# Lampduino-SMD-v001.net
KiCad netlist of a schematic drawn in EAGLE
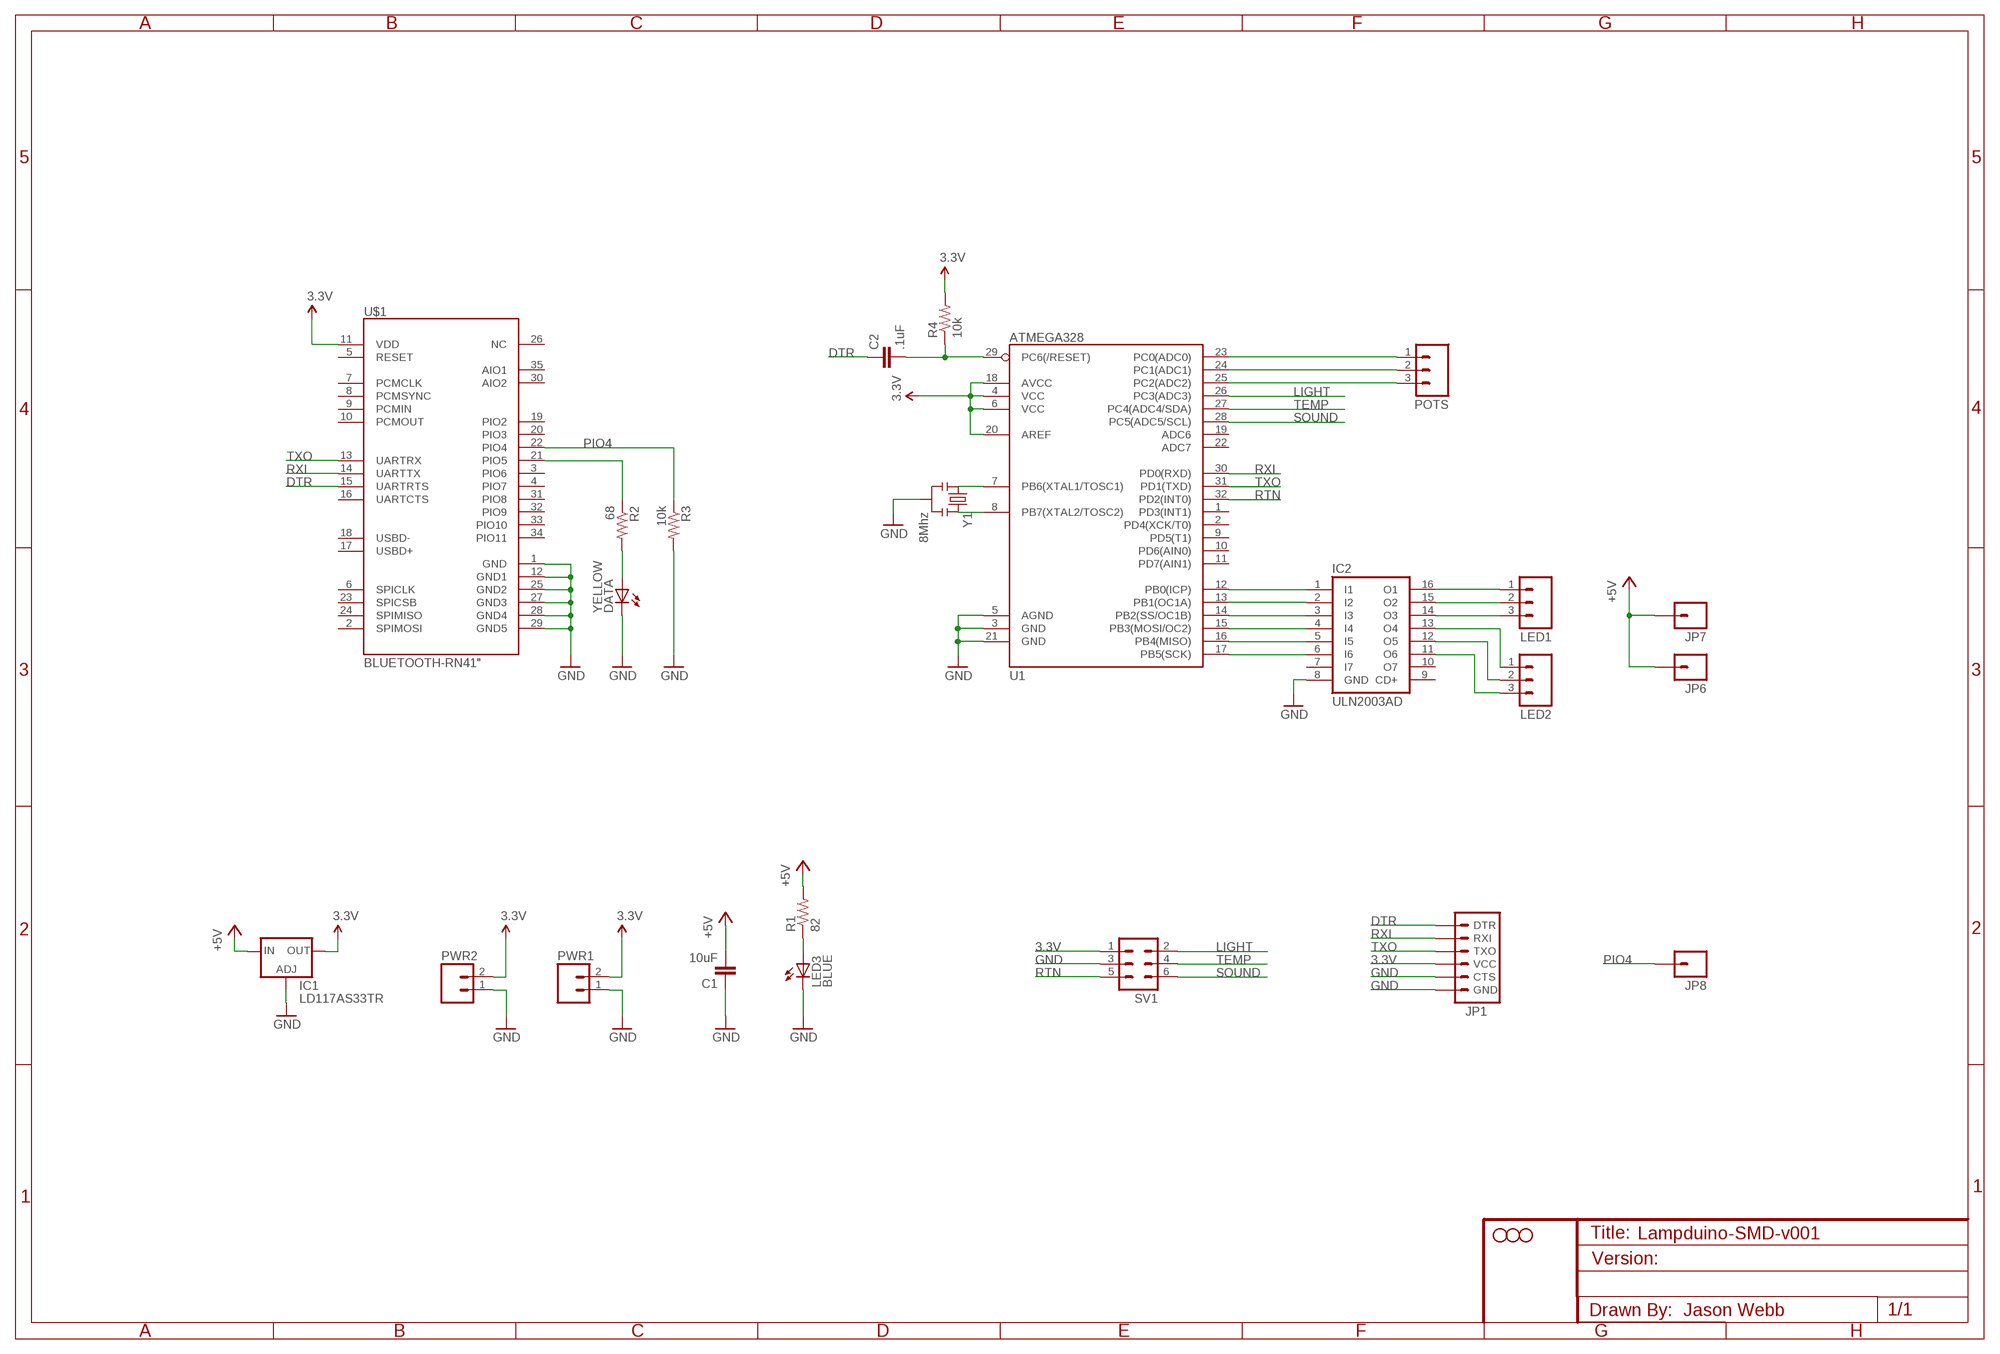
[diagram p0: schematic, sheet 1]

(export (version "E")
  (design (tool "Eeschema 10.0.6"))
  (components
    (comp (ref "C1")
      (value "10uF")
      (footprint "eagle-import:0805")
      (libsource (lib "eagle-import") (part "CAP0805"))
    )
    (comp (ref "C2")
      (value ".1uF")
      (footprint "eagle-import:0805")
      (libsource (lib "eagle-import") (part "CAP0805"))
    )
    (comp (ref "DATA")
      (value "YELLOW")
      (footprint "eagle-import:CHIPLED_0603")
      (libsource (lib "eagle-import") (part "LEDCHIPLED_0603"))
    )
    (comp (ref "IC1")
      (value "LD117AS33TR")
      (footprint "eagle-import:SOT223")
      (libsource (lib "eagle-import") (part "LD117A?S33TR"))
    )
    (comp (ref "IC2")
      (value "ULN2003AD")
      (footprint "eagle-import:SO16")
      (libsource (lib "eagle-import") (part "ULN2003AD"))
    )
    (comp (ref "JP1")
      (value "ARDUINO_SERIAL_PROGRAMLOCK")
      (footprint "eagle-import:1X06_LOCK")
      (libsource (lib "eagle-import") (part "ARDUINO_SERIAL_PROGRAMLOCK"))
    )
    (comp (ref "JP2")
      (value "STAND-OFFTIGHT")
      (footprint "eagle-import:STAND-OFF-TIGHT")
      (libsource (lib "eagle-import") (part "STAND-OFFTIGHT"))
    )
    (comp (ref "JP4")
      (value "STAND-OFFTIGHT")
      (footprint "eagle-import:STAND-OFF-TIGHT")
      (libsource (lib "eagle-import") (part "STAND-OFFTIGHT"))
    )
    (comp (ref "JP5")
      (value "STAND-OFFTIGHT")
      (footprint "eagle-import:STAND-OFF-TIGHT")
      (libsource (lib "eagle-import") (part "STAND-OFFTIGHT"))
    )
    (comp (ref "JP6")
      (value "M01PTH")
      (footprint "eagle-import:1X01")
      (libsource (lib "eagle-import") (part "M01PTH"))
    )
    (comp (ref "JP7")
      (value "M01PTH")
      (footprint "eagle-import:1X01")
      (libsource (lib "eagle-import") (part "M01PTH"))
    )
    (comp (ref "JP8")
      (value "M01PTH")
      (footprint "eagle-import:1X01")
      (libsource (lib "eagle-import") (part "M01PTH"))
    )
    (comp (ref "LED1")
      (value "M03PTH")
      (footprint "eagle-import:1X03")
      (libsource (lib "eagle-import") (part "M03PTH"))
    )
    (comp (ref "LED2")
      (value "M03PTH")
      (footprint "eagle-import:1X03")
      (libsource (lib "eagle-import") (part "M03PTH"))
    )
    (comp (ref "LED3")
      (value "BLUE")
      (footprint "eagle-import:CHIPLED_0603")
      (libsource (lib "eagle-import") (part "LEDCHIPLED_0603"))
    )
    (comp (ref "POTS")
      (value "M03PTH")
      (footprint "eagle-import:1X03")
      (libsource (lib "eagle-import") (part "M03PTH"))
    )
    (comp (ref "PWR1")
      (value "M02PTH")
      (footprint "eagle-import:1X02")
      (libsource (lib "eagle-import") (part "M02PTH"))
    )
    (comp (ref "PWR2")
      (value "M02PTH")
      (footprint "eagle-import:1X02")
      (libsource (lib "eagle-import") (part "M02PTH"))
    )
    (comp (ref "R1")
      (value "82")
      (footprint "eagle-import:R0603")
      (libsource (lib "eagle-import") (part "R-US_R0603"))
    )
    (comp (ref "R2")
      (value "68")
      (footprint "eagle-import:R0603")
      (libsource (lib "eagle-import") (part "R-US_R0603"))
    )
    (comp (ref "R3")
      (value "10k")
      (footprint "eagle-import:R0603")
      (libsource (lib "eagle-import") (part "R-US_R0603"))
    )
    (comp (ref "R4")
      (value "10k")
      (footprint "eagle-import:R0603")
      (libsource (lib "eagle-import") (part "R-US_R0603"))
    )
    (comp (ref "SV1")
      (value "ML6")
      (footprint "eagle-import:ML6")
      (libsource (lib "eagle-import") (part "ML6"))
    )
    (comp (ref "U$1")
      (value "BLUETOOTH-RN41\"")
      (footprint "eagle-import:RN41")
      (libsource (lib "eagle-import") (part "BLUETOOTH-RN41{dblquote}"))
    )
    (comp (ref "U1")
      (value "ATMEGA328")
      (footprint "eagle-import:TQFP32-08")
      (libsource (lib "eagle-import") (part "ATMEGA168"))
    )
    (comp (ref "Y1")
      (value "8Mhz")
      (footprint "eagle-import:RESONATOR-SMD")
      (libsource (lib "eagle-import") (part "RESONATORSMD"))
    )
  )
  (nets
    (net (code "1") (name "+5V") (class "Default")
      (node (ref "C1") (pin "2") (pinfunction "2_2") (pintype "passive"))
      (node (ref "IC1") (pin "3") (pinfunction "IN_3") (pintype "input"))
      (node (ref "JP6") (pin "1") (pinfunction "1_1") (pintype "passive"))
      (node (ref "JP7") (pin "1") (pinfunction "1_1") (pintype "passive"))
      (node (ref "R1") (pin "2") (pinfunction "2_2") (pintype "passive"))
    )
    (net (code "2") (name "/DTR") (class "Default")
      (node (ref "C2") (pin "1") (pinfunction "1_1") (pintype "passive"))
      (node (ref "JP1") (pin "1") (pinfunction "DTR_1") (pintype "passive"))
      (node (ref "U$1") (pin "15") (pinfunction "UARTRTS_15") (pintype "bidirectional"))
    )
    (net (code "3") (name "/LIGHT") (class "Default")
      (node (ref "SV1") (pin "2") (pinfunction "2_2") (pintype "passive"))
      (node (ref "U1") (pin "26") (pinfunction "PC3(ADC3)_26") (pintype "bidirectional"))
    )
    (net (code "4") (name "/PIO4") (class "Default")
      (node (ref "JP8") (pin "1") (pinfunction "1_1") (pintype "passive"))
      (node (ref "R3") (pin "1") (pinfunction "1_1") (pintype "passive"))
      (node (ref "U$1") (pin "22") (pinfunction "PIO4_22") (pintype "bidirectional"))
    )
    (net (code "5") (name "/RTN") (class "Default")
      (node (ref "SV1") (pin "5") (pinfunction "5_5") (pintype "passive"))
      (node (ref "U1") (pin "32") (pinfunction "PD2(INT0)_32") (pintype "bidirectional"))
    )
    (net (code "6") (name "/RXI") (class "Default")
      (node (ref "JP1") (pin "2") (pinfunction "RXI_2") (pintype "passive"))
      (node (ref "U$1") (pin "14") (pinfunction "UARTTX_14") (pintype "bidirectional"))
      (node (ref "U1") (pin "30") (pinfunction "PD0(RXD)_30") (pintype "bidirectional"))
    )
    (net (code "7") (name "/SOUND") (class "Default")
      (node (ref "SV1") (pin "6") (pinfunction "6_6") (pintype "passive"))
      (node (ref "U1") (pin "28") (pinfunction "PC5(ADC5/SCL)_28") (pintype "bidirectional"))
    )
    (net (code "8") (name "/TEMP") (class "Default")
      (node (ref "SV1") (pin "4") (pinfunction "4_4") (pintype "passive"))
      (node (ref "U1") (pin "27") (pinfunction "PC4(ADC4/SDA)_27") (pintype "bidirectional"))
    )
    (net (code "9") (name "/TXO") (class "Default")
      (node (ref "JP1") (pin "3") (pinfunction "TXO_3") (pintype "passive"))
      (node (ref "U$1") (pin "13") (pinfunction "UARTRX_13") (pintype "bidirectional"))
      (node (ref "U1") (pin "31") (pinfunction "PD1(TXD)_31") (pintype "bidirectional"))
    )
    (net (code "10") (name "3.3V") (class "Default")
      (node (ref "IC1") (pin "4") (pinfunction "OUT_4") (pintype "passive"))
      (node (ref "JP1") (pin "4") (pinfunction "VCC_4") (pintype "passive"))
      (node (ref "PWR1") (pin "2") (pinfunction "2_2") (pintype "passive"))
      (node (ref "PWR2") (pin "2") (pinfunction "2_2") (pintype "passive"))
      (node (ref "R4") (pin "2") (pinfunction "2_2") (pintype "passive"))
      (node (ref "SV1") (pin "1") (pinfunction "1_1") (pintype "passive"))
      (node (ref "U$1") (pin "11") (pinfunction "VDD_11") (pintype "bidirectional"))
      (node (ref "U1") (pin "18") (pinfunction "AVCC_18") (pintype "bidirectional"))
      (node (ref "U1") (pin "20") (pinfunction "AREF_20") (pintype "bidirectional"))
      (node (ref "U1") (pin "4") (pinfunction "VCC_4") (pintype "bidirectional"))
      (node (ref "U1") (pin "6") (pinfunction "VCC_6") (pintype "bidirectional"))
    )
    (net (code "11") (name "GND") (class "Default")
      (node (ref "C1") (pin "1") (pinfunction "1_1") (pintype "passive"))
      (node (ref "DATA") (pin "C") (pinfunction "C_C") (pintype "passive"))
      (node (ref "IC1") (pin "1") (pinfunction "ADJ_1") (pintype "input"))
      (node (ref "IC2") (pin "8") (pinfunction "GND_8") (pintype "power_in"))
      (node (ref "JP1") (pin "5") (pinfunction "CTS_5") (pintype "passive"))
      (node (ref "JP1") (pin "6") (pinfunction "GND_6") (pintype "passive"))
      (node (ref "LED3") (pin "C") (pinfunction "C_C") (pintype "passive"))
      (node (ref "PWR1") (pin "1") (pinfunction "1_1") (pintype "passive"))
      (node (ref "PWR2") (pin "1") (pinfunction "1_1") (pintype "passive"))
      (node (ref "R3") (pin "2") (pinfunction "2_2") (pintype "passive"))
      (node (ref "SV1") (pin "3") (pinfunction "3_3") (pintype "passive"))
      (node (ref "U$1") (pin "1") (pinfunction "GND_1") (pintype "bidirectional"))
      (node (ref "U$1") (pin "12") (pinfunction "GND1_12") (pintype "bidirectional"))
      (node (ref "U$1") (pin "25") (pinfunction "GND2_25") (pintype "bidirectional"))
      (node (ref "U$1") (pin "27") (pinfunction "GND3_27") (pintype "bidirectional"))
      (node (ref "U$1") (pin "28") (pinfunction "GND4_28") (pintype "bidirectional"))
      (node (ref "U$1") (pin "29") (pinfunction "GND5_29") (pintype "bidirectional"))
      (node (ref "U1") (pin "21") (pinfunction "GND_21") (pintype "bidirectional"))
      (node (ref "U1") (pin "3") (pinfunction "GND_3") (pintype "bidirectional"))
      (node (ref "U1") (pin "5") (pinfunction "AGND_5") (pintype "bidirectional"))
      (node (ref "Y1") (pin "2") (pinfunction "2_2") (pintype "passive"))
    )
    (net (code "12") (name "Net-(DATA-PadA)") (class "Default")
      (node (ref "DATA") (pin "A") (pinfunction "A_A") (pintype "passive"))
      (node (ref "R2") (pin "2") (pinfunction "2_2") (pintype "passive"))
    )
    (net (code "13") (name "Net-(IC2-I1)") (class "Default")
      (node (ref "IC2") (pin "1") (pinfunction "I1_1") (pintype "input"))
      (node (ref "U1") (pin "12") (pinfunction "PB0(ICP)_12") (pintype "bidirectional"))
    )
    (net (code "14") (name "Net-(IC2-I2)") (class "Default")
      (node (ref "IC2") (pin "2") (pinfunction "I2_2") (pintype "input"))
      (node (ref "U1") (pin "13") (pinfunction "PB1(OC1A)_13") (pintype "bidirectional"))
    )
    (net (code "15") (name "Net-(IC2-I3)") (class "Default")
      (node (ref "IC2") (pin "3") (pinfunction "I3_3") (pintype "input"))
      (node (ref "U1") (pin "14") (pinfunction "PB2(SS/OC1B)_14") (pintype "bidirectional"))
    )
    (net (code "16") (name "Net-(IC2-I4)") (class "Default")
      (node (ref "IC2") (pin "4") (pinfunction "I4_4") (pintype "input"))
      (node (ref "U1") (pin "15") (pinfunction "PB3(MOSI/OC2)_15") (pintype "bidirectional"))
    )
    (net (code "17") (name "Net-(IC2-I5)") (class "Default")
      (node (ref "IC2") (pin "5") (pinfunction "I5_5") (pintype "input"))
      (node (ref "U1") (pin "16") (pinfunction "PB4(MISO)_16") (pintype "bidirectional"))
    )
    (net (code "18") (name "Net-(IC2-I6)") (class "Default")
      (node (ref "IC2") (pin "6") (pinfunction "I6_6") (pintype "input"))
      (node (ref "U1") (pin "17") (pinfunction "PB5(SCK)_17") (pintype "bidirectional"))
    )
    (net (code "19") (name "Net-(IC2-O1)") (class "Default")
      (node (ref "IC2") (pin "16") (pinfunction "O1_16") (pintype "open_collector"))
      (node (ref "LED1") (pin "1") (pinfunction "1_1") (pintype "passive"))
    )
    (net (code "20") (name "Net-(IC2-O2)") (class "Default")
      (node (ref "IC2") (pin "15") (pinfunction "O2_15") (pintype "open_collector"))
      (node (ref "LED1") (pin "2") (pinfunction "2_2") (pintype "passive"))
    )
    (net (code "21") (name "Net-(IC2-O3)") (class "Default")
      (node (ref "IC2") (pin "14") (pinfunction "O3_14") (pintype "open_collector"))
      (node (ref "LED1") (pin "3") (pinfunction "3_3") (pintype "passive"))
    )
    (net (code "22") (name "Net-(IC2-O4)") (class "Default")
      (node (ref "IC2") (pin "13") (pinfunction "O4_13") (pintype "open_collector"))
      (node (ref "LED2") (pin "1") (pinfunction "1_1") (pintype "passive"))
    )
    (net (code "23") (name "Net-(IC2-O5)") (class "Default")
      (node (ref "IC2") (pin "12") (pinfunction "O5_12") (pintype "open_collector"))
      (node (ref "LED2") (pin "2") (pinfunction "2_2") (pintype "passive"))
    )
    (net (code "24") (name "Net-(IC2-O6)") (class "Default")
      (node (ref "IC2") (pin "11") (pinfunction "O6_11") (pintype "open_collector"))
      (node (ref "LED2") (pin "3") (pinfunction "3_3") (pintype "passive"))
    )
    (net (code "25") (name "Net-(LED3-PadA)") (class "Default")
      (node (ref "LED3") (pin "A") (pinfunction "A_A") (pintype "passive"))
      (node (ref "R1") (pin "1") (pinfunction "1_1") (pintype "passive"))
    )
    (net (code "26") (name "Net-(U$1-PIO5)") (class "Default")
      (node (ref "R2") (pin "1") (pinfunction "1_1") (pintype "passive"))
      (node (ref "U$1") (pin "21") (pinfunction "PIO5_21") (pintype "bidirectional"))
    )
    (net (code "27") (name "Net-(U1-PB6(XTAL1{slash}TOSC1))") (class "Default")
      (node (ref "U1") (pin "7") (pinfunction "PB6(XTAL1/TOSC1)_7") (pintype "bidirectional"))
      (node (ref "Y1") (pin "1") (pinfunction "1_1") (pintype "passive"))
    )
    (net (code "28") (name "Net-(U1-PB7(XTAL2{slash}TOSC2))") (class "Default")
      (node (ref "U1") (pin "8") (pinfunction "PB7(XTAL2/TOSC2)_8") (pintype "bidirectional"))
      (node (ref "Y1") (pin "3") (pinfunction "3_3") (pintype "passive"))
    )
    (net (code "29") (name "Net-(U1-PC0(ADC0))") (class "Default")
      (node (ref "POTS") (pin "1") (pinfunction "1_1") (pintype "passive"))
      (node (ref "U1") (pin "23") (pinfunction "PC0(ADC0)_23") (pintype "bidirectional"))
    )
    (net (code "30") (name "Net-(U1-PC1(ADC1))") (class "Default")
      (node (ref "POTS") (pin "2") (pinfunction "2_2") (pintype "passive"))
      (node (ref "U1") (pin "24") (pinfunction "PC1(ADC1)_24") (pintype "bidirectional"))
    )
    (net (code "31") (name "Net-(U1-PC2(ADC2))") (class "Default")
      (node (ref "POTS") (pin "3") (pinfunction "3_3") (pintype "passive"))
      (node (ref "U1") (pin "25") (pinfunction "PC2(ADC2)_25") (pintype "bidirectional"))
    )
    (net (code "32") (name "Net-(U1-PC6({slash}RESET))") (class "Default")
      (node (ref "C2") (pin "2") (pinfunction "2_2") (pintype "passive"))
      (node (ref "R4") (pin "1") (pinfunction "1_1") (pintype "passive"))
      (node (ref "U1") (pin "29") (pinfunction "PC6(/RESET)_29") (pintype "bidirectional"))
    )
    (net (code "33") (name "unconnected-(IC2-CD+-Pad9)") (class "Default")
      (node (ref "IC2") (pin "9") (pinfunction "CD+_9") (pintype "passive"))
    )
    (net (code "34") (name "unconnected-(IC2-I7-Pad7)") (class "Default")
      (node (ref "IC2") (pin "7") (pinfunction "I7_7") (pintype "input"))
    )
    (net (code "35") (name "unconnected-(IC2-O7-Pad10)") (class "Default")
      (node (ref "IC2") (pin "10") (pinfunction "O7_10") (pintype "open_collector"))
    )
    (net (code "36") (name "unconnected-(U$1-AIO1-Pad35)") (class "Default")
      (node (ref "U$1") (pin "35") (pinfunction "AIO1_35") (pintype "bidirectional"))
    )
    (net (code "37") (name "unconnected-(U$1-AIO2-Pad30)") (class "Default")
      (node (ref "U$1") (pin "30") (pinfunction "AIO2_30") (pintype "bidirectional"))
    )
    (net (code "38") (name "unconnected-(U$1-NC-Pad26)") (class "Default")
      (node (ref "U$1") (pin "26") (pinfunction "NC_26") (pintype "bidirectional"))
    )
    (net (code "39") (name "unconnected-(U$1-PCMCLK-Pad7)") (class "Default")
      (node (ref "U$1") (pin "7") (pinfunction "PCMCLK_7") (pintype "bidirectional"))
    )
    (net (code "40") (name "unconnected-(U$1-PCMIN-Pad9)") (class "Default")
      (node (ref "U$1") (pin "9") (pinfunction "PCMIN_9") (pintype "bidirectional"))
    )
    (net (code "41") (name "unconnected-(U$1-PCMOUT-Pad10)") (class "Default")
      (node (ref "U$1") (pin "10") (pinfunction "PCMOUT_10") (pintype "bidirectional"))
    )
    (net (code "42") (name "unconnected-(U$1-PCMSYNC-Pad8)") (class "Default")
      (node (ref "U$1") (pin "8") (pinfunction "PCMSYNC_8") (pintype "bidirectional"))
    )
    (net (code "43") (name "unconnected-(U$1-PIO2-Pad19)") (class "Default")
      (node (ref "U$1") (pin "19") (pinfunction "PIO2_19") (pintype "bidirectional"))
    )
    (net (code "44") (name "unconnected-(U$1-PIO3-Pad20)") (class "Default")
      (node (ref "U$1") (pin "20") (pinfunction "PIO3_20") (pintype "bidirectional"))
    )
    (net (code "45") (name "unconnected-(U$1-PIO6-Pad3)") (class "Default")
      (node (ref "U$1") (pin "3") (pinfunction "PIO6_3") (pintype "bidirectional"))
    )
    (net (code "46") (name "unconnected-(U$1-PIO7-Pad4)") (class "Default")
      (node (ref "U$1") (pin "4") (pinfunction "PIO7_4") (pintype "bidirectional"))
    )
    (net (code "47") (name "unconnected-(U$1-PIO8-Pad31)") (class "Default")
      (node (ref "U$1") (pin "31") (pinfunction "PIO8_31") (pintype "bidirectional"))
    )
    (net (code "48") (name "unconnected-(U$1-PIO9-Pad32)") (class "Default")
      (node (ref "U$1") (pin "32") (pinfunction "PIO9_32") (pintype "bidirectional"))
    )
    (net (code "49") (name "unconnected-(U$1-PIO10-Pad33)") (class "Default")
      (node (ref "U$1") (pin "33") (pinfunction "PIO10_33") (pintype "bidirectional"))
    )
    (net (code "50") (name "unconnected-(U$1-PIO11-Pad34)") (class "Default")
      (node (ref "U$1") (pin "34") (pinfunction "PIO11_34") (pintype "bidirectional"))
    )
    (net (code "51") (name "unconnected-(U$1-RESET-Pad5)") (class "Default")
      (node (ref "U$1") (pin "5") (pinfunction "RESET_5") (pintype "bidirectional"))
    )
    (net (code "52") (name "unconnected-(U$1-SPICLK-Pad6)") (class "Default")
      (node (ref "U$1") (pin "6") (pinfunction "SPICLK_6") (pintype "bidirectional"))
    )
    (net (code "53") (name "unconnected-(U$1-SPICSB-Pad23)") (class "Default")
      (node (ref "U$1") (pin "23") (pinfunction "SPICSB_23") (pintype "bidirectional"))
    )
    (net (code "54") (name "unconnected-(U$1-SPIMISO-Pad24)") (class "Default")
      (node (ref "U$1") (pin "24") (pinfunction "SPIMISO_24") (pintype "bidirectional"))
    )
    (net (code "55") (name "unconnected-(U$1-SPIMOSI-Pad2)") (class "Default")
      (node (ref "U$1") (pin "2") (pinfunction "SPIMOSI_2") (pintype "bidirectional"))
    )
    (net (code "56") (name "unconnected-(U$1-UARTCTS-Pad16)") (class "Default")
      (node (ref "U$1") (pin "16") (pinfunction "UARTCTS_16") (pintype "bidirectional"))
    )
    (net (code "57") (name "unconnected-(U$1-USBD+-Pad17)") (class "Default")
      (node (ref "U$1") (pin "17") (pinfunction "USBD+_17") (pintype "bidirectional"))
    )
    (net (code "58") (name "unconnected-(U$1-USBD--Pad18)") (class "Default")
      (node (ref "U$1") (pin "18") (pinfunction "USBD-_18") (pintype "bidirectional"))
    )
    (net (code "59") (name "unconnected-(U1-ADC6-Pad19)") (class "Default")
      (node (ref "U1") (pin "19") (pinfunction "ADC6_19") (pintype "bidirectional"))
    )
    (net (code "60") (name "unconnected-(U1-ADC7-Pad22)") (class "Default")
      (node (ref "U1") (pin "22") (pinfunction "ADC7_22") (pintype "bidirectional"))
    )
    (net (code "61") (name "unconnected-(U1-PD3(INT1)-Pad1)") (class "Default")
      (node (ref "U1") (pin "1") (pinfunction "PD3(INT1)_1") (pintype "bidirectional"))
    )
    (net (code "62") (name "unconnected-(U1-PD4(XCK{slash}T0)-Pad2)") (class "Default")
      (node (ref "U1") (pin "2") (pinfunction "PD4(XCK/T0)_2") (pintype "bidirectional"))
    )
    (net (code "63") (name "unconnected-(U1-PD5(T1)-Pad9)") (class "Default")
      (node (ref "U1") (pin "9") (pinfunction "PD5(T1)_9") (pintype "bidirectional"))
    )
    (net (code "64") (name "unconnected-(U1-PD6(AIN0)-Pad10)") (class "Default")
      (node (ref "U1") (pin "10") (pinfunction "PD6(AIN0)_10") (pintype "bidirectional"))
    )
    (net (code "65") (name "unconnected-(U1-PD7(AIN1)-Pad11)") (class "Default")
      (node (ref "U1") (pin "11") (pinfunction "PD7(AIN1)_11") (pintype "bidirectional"))
    )
  )
)
